# WatchDog.net
KiCad netlist of a schematic drawn in Altium Designer
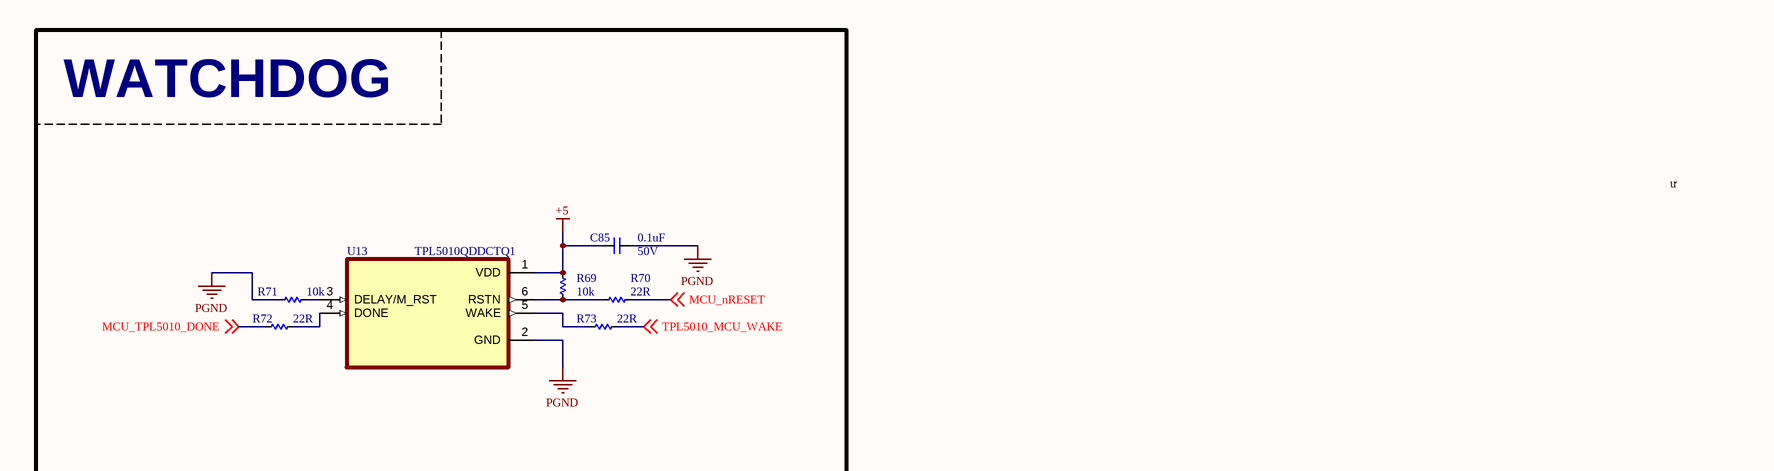
[diagram p0: WatchDog.SchDoc, left]

(export (version "E")
  (design (tool "Eeschema 10.0.6"))
  (components
    (comp (ref "C85")
      (value "0.1uF")
      (footprint "CAP_C_1608X80")
      (description "CAP")
      (fields (field (name "VOLTAGE") "50V"))
      (libsource (lib "LABLIB") (part "_CAP_C_2"))
    )
    (comp (ref "R69")
      (value "10k")
      (footprint "RES_C_1608X60")
      (description "RES")
      (libsource (lib "LABLIB") (part "_RES_B_2_2"))
    )
    (comp (ref "R70")
      (value "22R")
      (footprint "RES_C_1608X60")
      (description "RES")
      (libsource (lib "LABLIB") (part "_RES_B_2_2"))
    )
    (comp (ref "R71")
      (value "10k")
      (footprint "RES_C_1608X60")
      (description "RES")
      (libsource (lib "LABLIB") (part "_RES_B_2_2"))
    )
    (comp (ref "R72")
      (value "22R")
      (footprint "RES_C_1608X60")
      (description "RES")
      (libsource (lib "LABLIB") (part "_RES_B_2_2"))
    )
    (comp (ref "R73")
      (value "22R")
      (footprint "RES_C_1608X60")
      (description "RES")
      (libsource (lib "LABLIB") (part "_RES_B_2_2"))
    )
    (comp (ref "U13")
      (value "TPL5010QDDCTQ1")
      (footprint "SOT-23-THN-6")
      (libsource (lib "KIENASIY123_LIB") (part "TPL5010QDDCTQ1"))
    )
  )
  (nets
    (net (code "1") (name "+5") (class "Default")
      (node (ref "C85") (pin "2") (pinfunction "2_2") (pintype "passive"))
      (node (ref "R69") (pin "2") (pinfunction "2_2") (pintype "passive"))
      (node (ref "U13") (pin "1") (pinfunction "VDD_1") (pintype "power_in"))
    )
    (net (code "2") (name "MCU_TPL5010_DONE") (class "Default")
      (node (ref "R72") (pin "2") (pinfunction "2_2") (pintype "passive"))
    )
    (net (code "3") (name "MCU_nRESET") (class "Default")
      (node (ref "R70") (pin "1") (pinfunction "1_1") (pintype "passive"))
    )
    (net (code "4") (name "Net-(U13-DELAY{slash}M_RST)") (class "Default")
      (node (ref "R71") (pin "2") (pinfunction "2_2") (pintype "passive"))
      (node (ref "U13") (pin "3") (pinfunction "DELAY/M_RST_3") (pintype "input"))
    )
    (net (code "5") (name "Net-(U13-DONE)") (class "Default")
      (node (ref "R72") (pin "1") (pinfunction "1_1") (pintype "passive"))
      (node (ref "U13") (pin "4") (pinfunction "DONE_4") (pintype "input"))
    )
    (net (code "6") (name "Net-(U13-RSTN)") (class "Default")
      (node (ref "R69") (pin "1") (pinfunction "1_1") (pintype "passive"))
      (node (ref "R70") (pin "2") (pinfunction "2_2") (pintype "passive"))
      (node (ref "U13") (pin "6") (pinfunction "RSTN_6") (pintype "output"))
    )
    (net (code "7") (name "Net-(U13-WAKE)") (class "Default")
      (node (ref "R73") (pin "2") (pinfunction "2_2") (pintype "passive"))
      (node (ref "U13") (pin "5") (pinfunction "WAKE_5") (pintype "output"))
    )
    (net (code "8") (name "PGND") (class "Default")
      (node (ref "C85") (pin "1") (pinfunction "1_1") (pintype "passive"))
      (node (ref "R71") (pin "1") (pinfunction "1_1") (pintype "passive"))
      (node (ref "U13") (pin "2") (pinfunction "GND_2") (pintype "power_in"))
    )
    (net (code "9") (name "TPL5010_MCU_WAKE") (class "Default")
      (node (ref "R73") (pin "1") (pinfunction "1_1") (pintype "passive"))
    )
  )
)
